# vga2.net
KiCad netlist of a schematic drawn in EAGLE
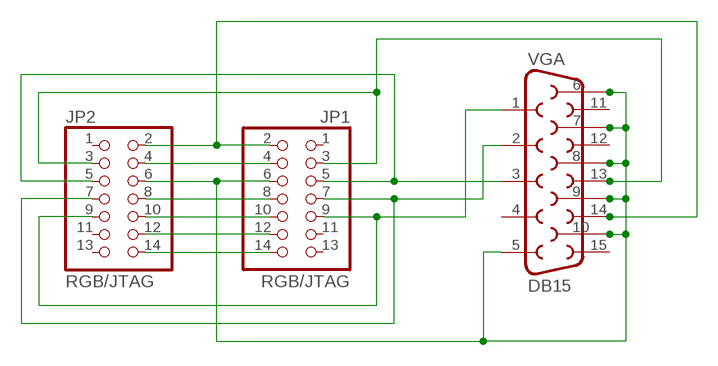
[diagram p0: schematic, sheet 1]

(export (version "E")
  (design (tool "Eeschema 10.0.6"))
  (components
    (comp (ref "JP1")
      (value "RGB/JTAG")
      (footprint "eagle-import:2X07")
      (libsource (lib "eagle-import") (part "PINHD-2X7"))
    )
    (comp (ref "JP2")
      (value "RGB/JTAG")
      (footprint "eagle-import:2X07")
      (libsource (lib "eagle-import") (part "PINHD-2X7"))
    )
    (comp (ref "VGA")
      (value "DB15")
      (footprint "eagle-import:DB15")
      (libsource (lib "eagle-import") (part "DB15"))
    )
  )
  (nets
    (net (code "1") (name "Net-(JP1-Pad2)") (class "Default")
      (node (ref "JP1") (pin "2") (pinfunction "2_2") (pintype "passive"))
      (node (ref "JP2") (pin "2") (pinfunction "2_2") (pintype "passive"))
      (node (ref "VGA") (pin "14") (pinfunction "14_14") (pintype "passive"))
    )
    (net (code "2") (name "Net-(JP1-Pad3)") (class "Default")
      (node (ref "JP1") (pin "3") (pinfunction "3_3") (pintype "passive"))
      (node (ref "JP2") (pin "3") (pinfunction "3_3") (pintype "passive"))
      (node (ref "VGA") (pin "13") (pinfunction "13_13") (pintype "passive"))
    )
    (net (code "3") (name "Net-(JP1-Pad4)") (class "Default")
      (node (ref "JP1") (pin "4") (pinfunction "4_4") (pintype "passive"))
      (node (ref "JP2") (pin "4") (pinfunction "4_4") (pintype "passive"))
    )
    (net (code "4") (name "Net-(JP1-Pad5)") (class "Default")
      (node (ref "JP1") (pin "5") (pinfunction "5_5") (pintype "passive"))
      (node (ref "JP2") (pin "5") (pinfunction "5_5") (pintype "passive"))
      (node (ref "VGA") (pin "3") (pinfunction "3_3") (pintype "passive"))
    )
    (net (code "5") (name "Net-(JP1-Pad6)") (class "Default")
      (node (ref "JP1") (pin "6") (pinfunction "6_6") (pintype "passive"))
      (node (ref "JP2") (pin "6") (pinfunction "6_6") (pintype "passive"))
      (node (ref "VGA") (pin "10") (pinfunction "10_10") (pintype "passive"))
      (node (ref "VGA") (pin "5") (pinfunction "5_5") (pintype "passive"))
      (node (ref "VGA") (pin "6") (pinfunction "6_6") (pintype "passive"))
      (node (ref "VGA") (pin "7") (pinfunction "7_7") (pintype "passive"))
      (node (ref "VGA") (pin "8") (pinfunction "8_8") (pintype "passive"))
      (node (ref "VGA") (pin "9") (pinfunction "9_9") (pintype "passive"))
    )
    (net (code "6") (name "Net-(JP1-Pad7)") (class "Default")
      (node (ref "JP1") (pin "7") (pinfunction "7_7") (pintype "passive"))
      (node (ref "JP2") (pin "7") (pinfunction "7_7") (pintype "passive"))
      (node (ref "VGA") (pin "2") (pinfunction "2_2") (pintype "passive"))
    )
    (net (code "7") (name "Net-(JP1-Pad8)") (class "Default")
      (node (ref "JP1") (pin "8") (pinfunction "8_8") (pintype "passive"))
      (node (ref "JP2") (pin "8") (pinfunction "8_8") (pintype "passive"))
    )
    (net (code "8") (name "Net-(JP1-Pad9)") (class "Default")
      (node (ref "JP1") (pin "9") (pinfunction "9_9") (pintype "passive"))
      (node (ref "JP2") (pin "9") (pinfunction "9_9") (pintype "passive"))
      (node (ref "VGA") (pin "1") (pinfunction "1_1") (pintype "passive"))
    )
    (net (code "9") (name "Net-(JP1-Pad10)") (class "Default")
      (node (ref "JP1") (pin "10") (pinfunction "10_10") (pintype "passive"))
      (node (ref "JP2") (pin "10") (pinfunction "10_10") (pintype "passive"))
    )
    (net (code "10") (name "Net-(JP1-Pad12)") (class "Default")
      (node (ref "JP1") (pin "12") (pinfunction "12_12") (pintype "passive"))
      (node (ref "JP2") (pin "12") (pinfunction "12_12") (pintype "passive"))
    )
    (net (code "11") (name "Net-(JP1-Pad14)") (class "Default")
      (node (ref "JP1") (pin "14") (pinfunction "14_14") (pintype "passive"))
      (node (ref "JP2") (pin "14") (pinfunction "14_14") (pintype "passive"))
    )
    (net (code "12") (name "unconnected-(JP1-Pad1)") (class "Default")
      (node (ref "JP1") (pin "1") (pinfunction "1_1") (pintype "passive"))
    )
    (net (code "13") (name "unconnected-(JP1-Pad11)") (class "Default")
      (node (ref "JP1") (pin "11") (pinfunction "11_11") (pintype "passive"))
    )
    (net (code "14") (name "unconnected-(JP1-Pad13)") (class "Default")
      (node (ref "JP1") (pin "13") (pinfunction "13_13") (pintype "passive"))
    )
    (net (code "15") (name "unconnected-(JP2-Pad1)") (class "Default")
      (node (ref "JP2") (pin "1") (pinfunction "1_1") (pintype "passive"))
    )
    (net (code "16") (name "unconnected-(JP2-Pad11)") (class "Default")
      (node (ref "JP2") (pin "11") (pinfunction "11_11") (pintype "passive"))
    )
    (net (code "17") (name "unconnected-(JP2-Pad13)") (class "Default")
      (node (ref "JP2") (pin "13") (pinfunction "13_13") (pintype "passive"))
    )
    (net (code "18") (name "unconnected-(VGA-Pad4)") (class "Default")
      (node (ref "VGA") (pin "4") (pinfunction "4_4") (pintype "passive"))
    )
    (net (code "19") (name "unconnected-(VGA-Pad11)") (class "Default")
      (node (ref "VGA") (pin "11") (pinfunction "11_11") (pintype "passive"))
    )
    (net (code "20") (name "unconnected-(VGA-Pad12)") (class "Default")
      (node (ref "VGA") (pin "12") (pinfunction "12_12") (pintype "passive"))
    )
    (net (code "21") (name "unconnected-(VGA-Pad15)") (class "Default")
      (node (ref "VGA") (pin "15") (pinfunction "15_15") (pintype "passive"))
    )
  )
)
